# Controller.net
KiCad netlist of a schematic drawn in Altium Designer
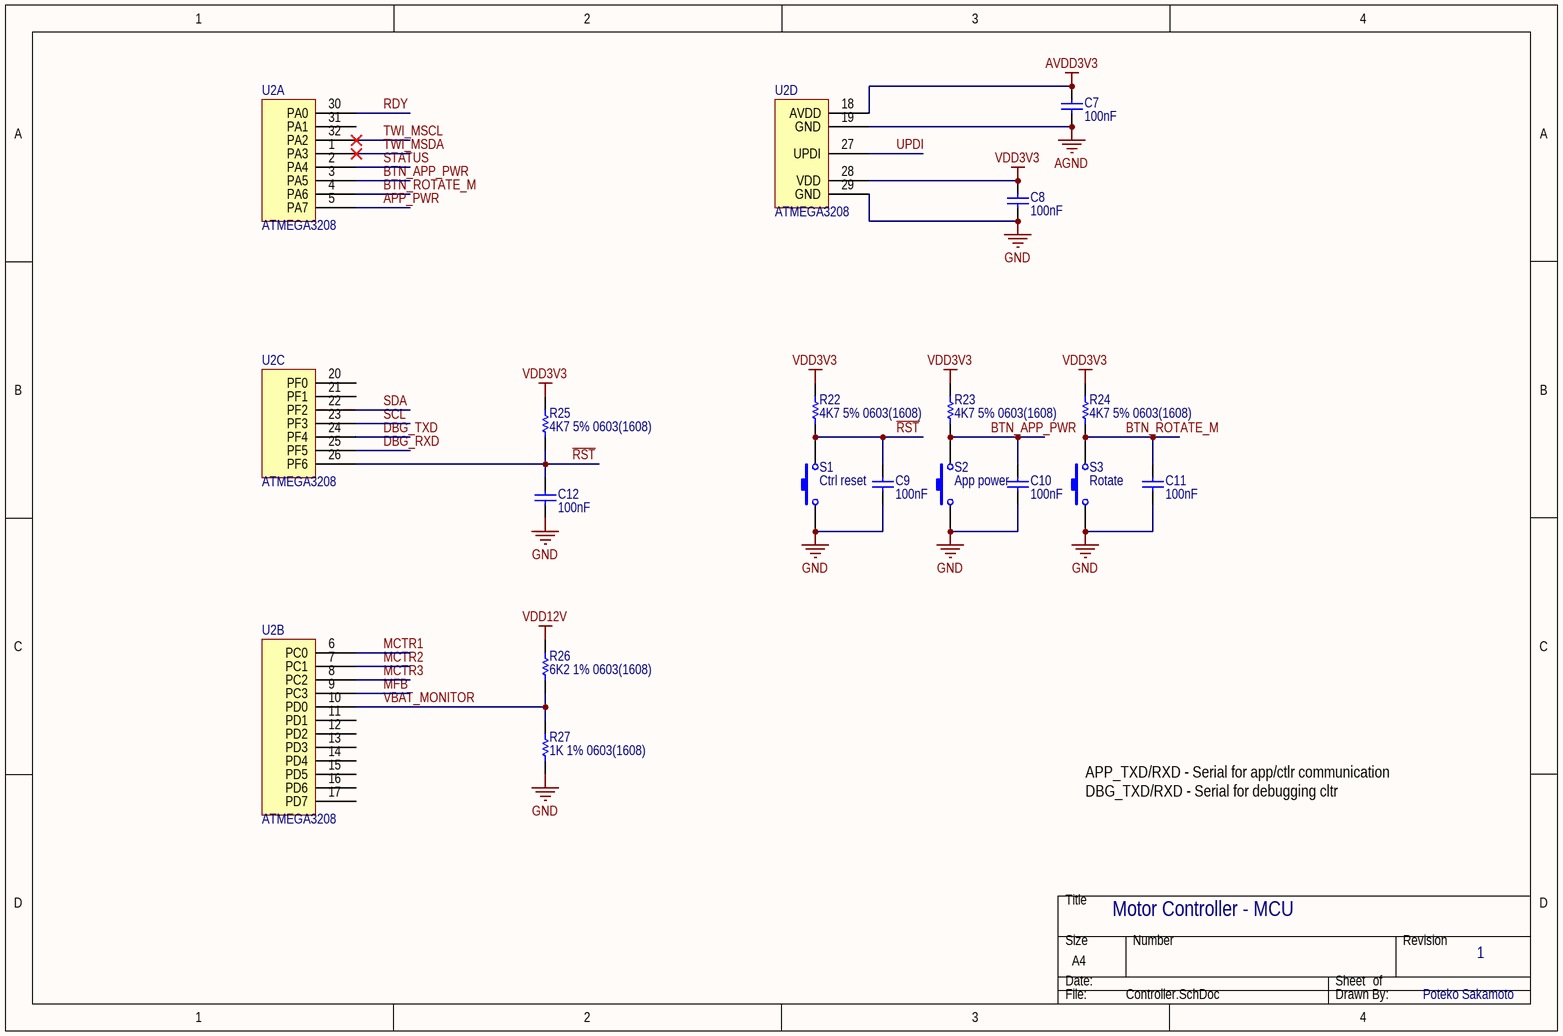
[diagram p0: Controller.SchDoc]

(export (version "E")
  (design (tool "Eeschema 10.0.6"))
  (components
    (comp (ref "C7")
      (value "100nF")
      (footprint "CAPC0603(1608)100_M")
      (description "CAP 100nF 50V ±10% 0603 (1608 Metric) Thickness 1mm SMD")
      (fields (field (name "TOLERANCE") "Â±10%"))
      (libsource (lib "Altium Content Vault") (part "CAP"))
    )
    (comp (ref "C8")
      (value "100nF")
      (footprint "CAPC0603(1608)100_M")
      (description "CAP 100nF 50V ±10% 0603 (1608 Metric) Thickness 1mm SMD")
      (fields (field (name "TOLERANCE") "Â±10%"))
      (libsource (lib "Altium Content Vault") (part "CAP"))
    )
    (comp (ref "C9")
      (value "100nF")
      (footprint "CAPC0603(1608)100_M")
      (description "CAP 100nF 50V ±10% 0603 (1608 Metric) Thickness 1mm SMD")
      (fields (field (name "TOLERANCE") "Â±10%"))
      (libsource (lib "Altium Content Vault") (part "CAP"))
    )
    (comp (ref "C10")
      (value "100nF")
      (footprint "CAPC0603(1608)100_M")
      (description "CAP 100nF 50V ±10% 0603 (1608 Metric) Thickness 1mm SMD")
      (fields (field (name "TOLERANCE") "Â±10%"))
      (libsource (lib "Altium Content Vault") (part "CAP"))
    )
    (comp (ref "C11")
      (value "100nF")
      (footprint "CAPC0603(1608)100_M")
      (description "CAP 100nF 50V ±10% 0603 (1608 Metric) Thickness 1mm SMD")
      (fields (field (name "TOLERANCE") "Â±10%"))
      (libsource (lib "Altium Content Vault") (part "CAP"))
    )
    (comp (ref "C12")
      (value "100nF")
      (footprint "CAPC0603(1608)100_M")
      (description "CAP 100nF 50V ±10% 0603 (1608 Metric) Thickness 1mm SMD")
      (fields (field (name "TOLERANCE") "Â±10%"))
      (libsource (lib "Altium Content Vault") (part "CAP"))
    )
    (comp (ref "R22")
      (value "4K7 5% 0603(1608)")
      (footprint "RESC0603(1608)_M")
      (description "4K7 0.1W 5% 0603 (1608 Metric)  SMD")
      (fields (field (name "TOLERANCE") "5 %") (field (name "POWER") "0.1 W"))
      (libsource (lib "Altium Content Vault") (part "RES"))
    )
    (comp (ref "R23")
      (value "4K7 5% 0603(1608)")
      (footprint "RESC0603(1608)_M")
      (description "4K7 0.1W 5% 0603 (1608 Metric)  SMD")
      (fields (field (name "TOLERANCE") "5 %") (field (name "POWER") "0.1 W"))
      (libsource (lib "Altium Content Vault") (part "RES"))
    )
    (comp (ref "R24")
      (value "4K7 5% 0603(1608)")
      (footprint "RESC0603(1608)_M")
      (description "4K7 0.1W 5% 0603 (1608 Metric)  SMD")
      (fields (field (name "TOLERANCE") "5 %") (field (name "POWER") "0.1 W"))
      (libsource (lib "Altium Content Vault") (part "RES"))
    )
    (comp (ref "R25")
      (value "4K7 5% 0603(1608)")
      (footprint "RESC0603(1608)_M")
      (description "4K7 0.1W 5% 0603 (1608 Metric)  SMD")
      (fields (field (name "TOLERANCE") "5 %") (field (name "POWER") "0.1 W"))
      (libsource (lib "Altium Content Vault") (part "RES"))
    )
    (comp (ref "R26")
      (value "6K2 1% 0603(1608)")
      (footprint "RESC0603(1608)_M")
      (description "6K2 0.1W 1% 0603 (1608 Metric)  SMD")
      (fields (field (name "TOLERANCE") "1 %") (field (name "POWER") "0.1 W"))
      (libsource (lib "Altium Content Vault") (part "RES"))
    )
    (comp (ref "R27")
      (value "1K 1% 0603(1608)")
      (footprint "RESC0603(1608)_M")
      (description "1K 0.1W 1% 0603 (1608 Metric)  SMD")
      (fields (field (name "TOLERANCE") "1 %") (field (name "POWER") "0.1 W"))
      (libsource (lib "Altium Content Vault") (part "RES"))
    )
    (comp (ref "S1")
      (value "Ctrl reset")
      (footprint "SMD Button")
      (description "Switch")
      (fields (field (name "PUBLISHER") "Altium Limited"))
      (libsource (lib "Miscellaneous Devices") (part "SW-PB"))
    )
    (comp (ref "S2")
      (value "App power")
      (footprint "SMD Button")
      (description "Switch")
      (fields (field (name "PUBLISHER") "Altium Limited"))
      (libsource (lib "Miscellaneous Devices") (part "SW-PB"))
    )
    (comp (ref "S3")
      (value "Rotate")
      (footprint "SMD Button")
      (description "Switch")
      (fields (field (name "PUBLISHER") "Altium Limited"))
      (libsource (lib "Miscellaneous Devices") (part "SW-PB"))
    )
    (comp (ref "U2")
      (value "ATMEGA3208")
      (footprint "QFP80P900X900X120-32N")
      (libsource (lib "SamacSys") (part "ATMEGA3208"))
    )
  )
  (nets
    (net (code "1") (name "/APP_PWR") (class "Default")
      (node (ref "U2") (pin "5") (pinfunction "PA7_5") (pintype "passive"))
    )
    (net (code "2") (name "/BTN_APP_PWR") (class "Default")
      (node (ref "C10") (pin "2") (pinfunction "2_2") (pintype "passive"))
      (node (ref "R23") (pin "1") (pinfunction "1_1") (pintype "passive"))
      (node (ref "S2") (pin "2") (pinfunction "2_2") (pintype "passive"))
      (node (ref "U2") (pin "3") (pinfunction "PA5_3") (pintype "passive"))
    )
    (net (code "3") (name "/BTN_ROTATE_M") (class "Default")
      (node (ref "C11") (pin "2") (pinfunction "2_2") (pintype "passive"))
      (node (ref "R24") (pin "1") (pinfunction "1_1") (pintype "passive"))
      (node (ref "S3") (pin "2") (pinfunction "2_2") (pintype "passive"))
      (node (ref "U2") (pin "4") (pinfunction "PA6_4") (pintype "passive"))
    )
    (net (code "4") (name "/DBG_RXD") (class "Default")
      (node (ref "U2") (pin "25") (pinfunction "PF5_25") (pintype "passive"))
    )
    (net (code "5") (name "/DBG_TXD") (class "Default")
      (node (ref "U2") (pin "24") (pinfunction "PF4_24") (pintype "passive"))
    )
    (net (code "6") (name "/MCTR1") (class "Default")
      (node (ref "U2") (pin "6") (pinfunction "PC0_6") (pintype "passive"))
    )
    (net (code "7") (name "/MCTR2") (class "Default")
      (node (ref "U2") (pin "7") (pinfunction "PC1_7") (pintype "passive"))
    )
    (net (code "8") (name "/MCTR3") (class "Default")
      (node (ref "U2") (pin "8") (pinfunction "PC2_8") (pintype "passive"))
    )
    (net (code "9") (name "/MFB") (class "Default")
      (node (ref "U2") (pin "9") (pinfunction "PC3_9") (pintype "passive"))
    )
    (net (code "10") (name "/RDY") (class "Default")
      (node (ref "U2") (pin "30") (pinfunction "PA0_30") (pintype "passive"))
    )
    (net (code "11") (name "/SCL") (class "Default")
      (node (ref "U2") (pin "23") (pinfunction "PF3_23") (pintype "passive"))
    )
    (net (code "12") (name "/SDA") (class "Default")
      (node (ref "U2") (pin "22") (pinfunction "PF2_22") (pintype "passive"))
    )
    (net (code "13") (name "/STATUS") (class "Default")
      (node (ref "U2") (pin "2") (pinfunction "PA4_2") (pintype "passive"))
    )
    (net (code "14") (name "/TWI_MSCL") (class "Default")
      (node (ref "U2") (pin "32") (pinfunction "PA2_32") (pintype "passive+no_connect"))
    )
    (net (code "15") (name "/TWI_MSDA") (class "Default")
      (node (ref "U2") (pin "1") (pinfunction "PA3_1") (pintype "passive+no_connect"))
    )
    (net (code "16") (name "/UPDI") (class "Default")
      (node (ref "U2") (pin "27") (pinfunction "UPDI_27") (pintype "passive"))
    )
    (net (code "17") (name "/VBAT_MONITOR") (class "Default")
      (node (ref "R26") (pin "1") (pinfunction "1_1") (pintype "passive"))
      (node (ref "R27") (pin "2") (pinfunction "2_2") (pintype "passive"))
      (node (ref "U2") (pin "10") (pinfunction "PD0_10") (pintype "passive"))
    )
    (net (code "18") (name "/~{RST}") (class "Default")
      (node (ref "C12") (pin "2") (pinfunction "2_2") (pintype "passive"))
      (node (ref "C9") (pin "2") (pinfunction "2_2") (pintype "passive"))
      (node (ref "R22") (pin "1") (pinfunction "1_1") (pintype "passive"))
      (node (ref "R25") (pin "1") (pinfunction "1_1") (pintype "passive"))
      (node (ref "S1") (pin "2") (pinfunction "2_2") (pintype "passive"))
      (node (ref "U2") (pin "26") (pinfunction "PF6_26") (pintype "passive"))
    )
    (net (code "19") (name "AGND") (class "Default")
      (node (ref "C7") (pin "1") (pinfunction "1_1") (pintype "passive"))
      (node (ref "U2") (pin "19") (pinfunction "GND_19") (pintype "passive"))
    )
    (net (code "20") (name "AVDD3V3") (class "Default")
      (node (ref "C7") (pin "2") (pinfunction "2_2") (pintype "passive"))
      (node (ref "U2") (pin "18") (pinfunction "AVDD_18") (pintype "passive"))
    )
    (net (code "21") (name "GND") (class "Default")
      (node (ref "C10") (pin "1") (pinfunction "1_1") (pintype "passive"))
      (node (ref "C11") (pin "1") (pinfunction "1_1") (pintype "passive"))
      (node (ref "C12") (pin "1") (pinfunction "1_1") (pintype "passive"))
      (node (ref "C8") (pin "1") (pinfunction "1_1") (pintype "passive"))
      (node (ref "C9") (pin "1") (pinfunction "1_1") (pintype "passive"))
      (node (ref "R27") (pin "1") (pinfunction "1_1") (pintype "passive"))
      (node (ref "S1") (pin "1") (pinfunction "1_1") (pintype "passive"))
      (node (ref "S2") (pin "1") (pinfunction "1_1") (pintype "passive"))
      (node (ref "S3") (pin "1") (pinfunction "1_1") (pintype "passive"))
      (node (ref "U2") (pin "29") (pinfunction "GND_29") (pintype "passive"))
    )
    (net (code "22") (name "VDD3V3") (class "Default")
      (node (ref "C8") (pin "2") (pinfunction "2_2") (pintype "passive"))
      (node (ref "R22") (pin "2") (pinfunction "2_2") (pintype "passive"))
      (node (ref "R23") (pin "2") (pinfunction "2_2") (pintype "passive"))
      (node (ref "R24") (pin "2") (pinfunction "2_2") (pintype "passive"))
      (node (ref "R25") (pin "2") (pinfunction "2_2") (pintype "passive"))
      (node (ref "U2") (pin "28") (pinfunction "VDD_28") (pintype "passive"))
    )
    (net (code "23") (name "VDD12V") (class "Default")
      (node (ref "R26") (pin "2") (pinfunction "2_2") (pintype "passive"))
    )
    (net (code "24") (name "unconnected-(U2A-PA1-Pad31)") (class "Default")
      (node (ref "U2") (pin "31") (pinfunction "PA1_31") (pintype "passive"))
    )
    (net (code "25") (name "unconnected-(U2B-PD1-Pad11)") (class "Default")
      (node (ref "U2") (pin "11") (pinfunction "PD1_11") (pintype "passive"))
    )
    (net (code "26") (name "unconnected-(U2B-PD2-Pad12)") (class "Default")
      (node (ref "U2") (pin "12") (pinfunction "PD2_12") (pintype "passive"))
    )
    (net (code "27") (name "unconnected-(U2B-PD3-Pad13)") (class "Default")
      (node (ref "U2") (pin "13") (pinfunction "PD3_13") (pintype "passive"))
    )
    (net (code "28") (name "unconnected-(U2B-PD4-Pad14)") (class "Default")
      (node (ref "U2") (pin "14") (pinfunction "PD4_14") (pintype "passive"))
    )
    (net (code "29") (name "unconnected-(U2B-PD5-Pad15)") (class "Default")
      (node (ref "U2") (pin "15") (pinfunction "PD5_15") (pintype "passive"))
    )
    (net (code "30") (name "unconnected-(U2B-PD6-Pad16)") (class "Default")
      (node (ref "U2") (pin "16") (pinfunction "PD6_16") (pintype "passive"))
    )
    (net (code "31") (name "unconnected-(U2B-PD7-Pad17)") (class "Default")
      (node (ref "U2") (pin "17") (pinfunction "PD7_17") (pintype "passive"))
    )
    (net (code "32") (name "unconnected-(U2C-PF0-Pad20)") (class "Default")
      (node (ref "U2") (pin "20") (pinfunction "PF0_20") (pintype "passive"))
    )
    (net (code "33") (name "unconnected-(U2C-PF1-Pad21)") (class "Default")
      (node (ref "U2") (pin "21") (pinfunction "PF1_21") (pintype "passive"))
    )
  )
)
